# TP_IHM_CONNECTOR.net
KiCad netlist of a schematic drawn in Altium Designer
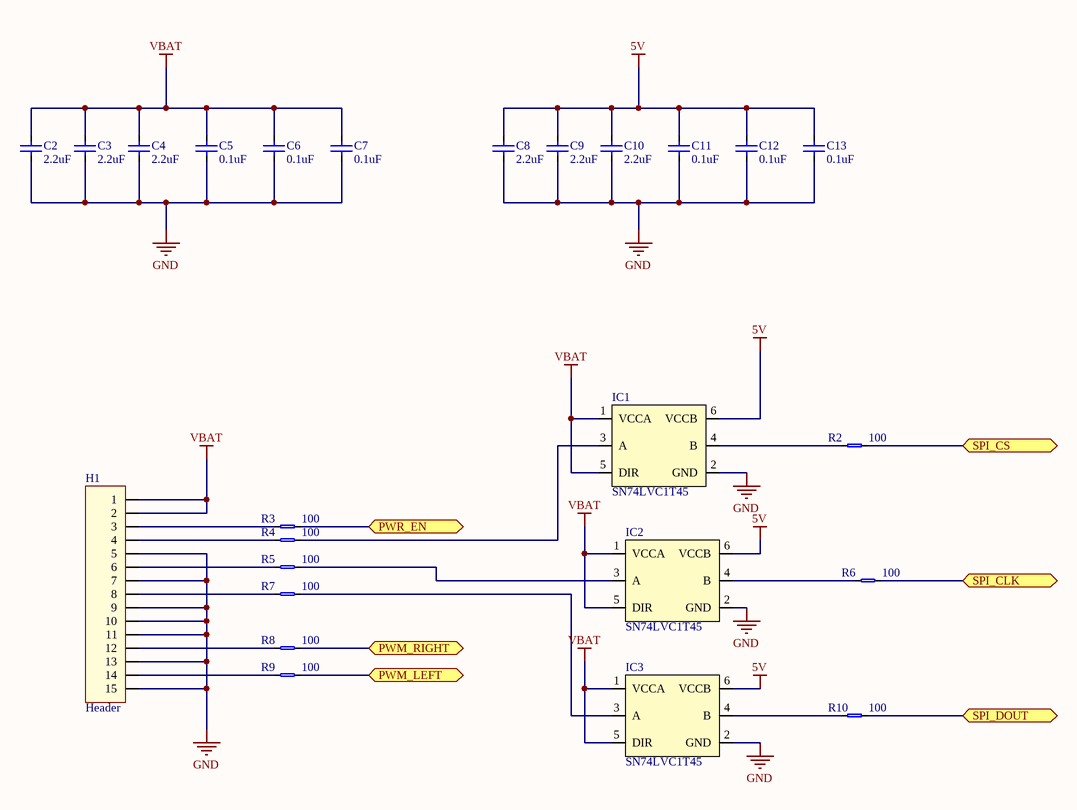
[diagram p0: TP_IHM_CONNECTOR.SchDoc]

(export (version "E")
  (design (tool "Eeschema 10.0.6"))
  (components
    (comp (ref "C2")
      (value "2.2uF")
      (footprint "0402_CAP_LD")
      (description "Ceramic Capacitor")
      (fields (field (name "Comment") "CerCap"))
      (libsource (lib "TpGivenLib") (part "CerCap"))
    )
    (comp (ref "C3")
      (value "2.2uF")
      (footprint "0402_CAP_LD")
      (description "Ceramic Capacitor")
      (fields (field (name "Comment") "CerCap"))
      (libsource (lib "TpGivenLib") (part "CerCap"))
    )
    (comp (ref "C4")
      (value "2.2uF")
      (footprint "0402_CAP_LD")
      (description "Ceramic Capacitor")
      (fields (field (name "Comment") "CerCap"))
      (libsource (lib "TpGivenLib") (part "CerCap"))
    )
    (comp (ref "C5")
      (value "0.1uF")
      (footprint "0402_CAP_LD")
      (description "Ceramic Capacitor")
      (fields (field (name "Comment") "CerCap"))
      (libsource (lib "TpGivenLib") (part "CerCap"))
    )
    (comp (ref "C6")
      (value "0.1uF")
      (footprint "0402_CAP_LD")
      (description "Ceramic Capacitor")
      (fields (field (name "Comment") "CerCap"))
      (libsource (lib "TpGivenLib") (part "CerCap"))
    )
    (comp (ref "C7")
      (value "0.1uF")
      (footprint "0402_CAP_LD")
      (description "Ceramic Capacitor")
      (fields (field (name "Comment") "CerCap"))
      (libsource (lib "TpGivenLib") (part "CerCap"))
    )
    (comp (ref "C8")
      (value "2.2uF")
      (footprint "0402_CAP_LD")
      (description "Ceramic Capacitor")
      (fields (field (name "Comment") "CerCap"))
      (libsource (lib "TpGivenLib") (part "CerCap"))
    )
    (comp (ref "C9")
      (value "2.2uF")
      (footprint "0402_CAP_LD")
      (description "Ceramic Capacitor")
      (fields (field (name "Comment") "CerCap"))
      (libsource (lib "TpGivenLib") (part "CerCap"))
    )
    (comp (ref "C10")
      (value "2.2uF")
      (footprint "0402_CAP_LD")
      (description "Ceramic Capacitor")
      (fields (field (name "Comment") "CerCap"))
      (libsource (lib "TpGivenLib") (part "CerCap"))
    )
    (comp (ref "C11")
      (value "0.1uF")
      (footprint "0402_CAP_LD")
      (description "Ceramic Capacitor")
      (fields (field (name "Comment") "CerCap"))
      (libsource (lib "TpGivenLib") (part "CerCap"))
    )
    (comp (ref "C12")
      (value "0.1uF")
      (footprint "0402_CAP_LD")
      (description "Ceramic Capacitor")
      (fields (field (name "Comment") "CerCap"))
      (libsource (lib "TpGivenLib") (part "CerCap"))
    )
    (comp (ref "C13")
      (value "0.1uF")
      (footprint "0402_CAP_LD")
      (description "Ceramic Capacitor")
      (fields (field (name "Comment") "CerCap"))
      (libsource (lib "TpGivenLib") (part "CerCap"))
    )
    (comp (ref "H1")
      (value "Header")
      (footprint "653115131822")
      (description "Header 15x1")
      (libsource (lib "TpGiven") (part "HEADER_15x1"))
    )
    (comp (ref "IC1")
      (value "SN74LVC1T45")
      (footprint "MO-203AB_LD")
      (description "Single Bit Dual Supply Buffer")
      (libsource (lib "TpGiven") (part "SN74LVC1T45"))
    )
    (comp (ref "IC2")
      (value "SN74LVC1T45")
      (footprint "MO-203AB_LD")
      (description "Single Bit Dual Supply Buffer")
      (libsource (lib "TpGiven") (part "SN74LVC1T45"))
    )
    (comp (ref "IC3")
      (value "SN74LVC1T45")
      (footprint "MO-203AB_LD")
      (description "Single Bit Dual Supply Buffer")
      (libsource (lib "TpGiven") (part "SN74LVC1T45"))
    )
    (comp (ref "R2")
      (value "100")
      (footprint "0603_RES_LD")
      (description "Resistor")
      (libsource (lib "TpGiven") (part "Resistor"))
    )
    (comp (ref "R3")
      (value "100")
      (footprint "0603_RES_LD")
      (description "Resistor")
      (libsource (lib "TpGiven") (part "Resistor"))
    )
    (comp (ref "R4")
      (value "100")
      (footprint "0603_RES_LD")
      (description "Resistor")
      (libsource (lib "TpGiven") (part "Resistor"))
    )
    (comp (ref "R5")
      (value "100")
      (footprint "0603_RES_LD")
      (description "Resistor")
      (libsource (lib "TpGiven") (part "Resistor"))
    )
    (comp (ref "R6")
      (value "100")
      (footprint "0603_RES_LD")
      (description "Resistor")
      (libsource (lib "TpGiven") (part "Resistor"))
    )
    (comp (ref "R7")
      (value "100")
      (footprint "0603_RES_LD")
      (description "Resistor")
      (libsource (lib "TpGiven") (part "Resistor"))
    )
    (comp (ref "R8")
      (value "100")
      (footprint "0603_RES_LD")
      (description "Resistor")
      (libsource (lib "TpGiven") (part "Resistor"))
    )
    (comp (ref "R9")
      (value "100")
      (footprint "0603_RES_LD")
      (description "Resistor")
      (libsource (lib "TpGiven") (part "Resistor"))
    )
    (comp (ref "R10")
      (value "100")
      (footprint "0603_RES_LD")
      (description "Resistor")
      (libsource (lib "TpGiven") (part "Resistor"))
    )
  )
  (nets
    (net (code "1") (name "/PWM_LEFT") (class "Default")
      (node (ref "R9") (pin "2") (pinfunction "2_2") (pintype "passive"))
    )
    (net (code "2") (name "/PWM_RIGHT") (class "Default")
      (node (ref "R8") (pin "2") (pinfunction "2_2") (pintype "passive"))
    )
    (net (code "3") (name "/PWR_EN") (class "Default")
      (node (ref "R3") (pin "2") (pinfunction "2_2") (pintype "passive"))
    )
    (net (code "4") (name "/SPI_CLK") (class "Default")
      (node (ref "R6") (pin "2") (pinfunction "2_2") (pintype "passive"))
    )
    (net (code "5") (name "/SPI_CS") (class "Default")
      (node (ref "R2") (pin "2") (pinfunction "2_2") (pintype "passive"))
    )
    (net (code "6") (name "/SPI_DOUT") (class "Default")
      (node (ref "R10") (pin "2") (pinfunction "2_2") (pintype "passive"))
    )
    (net (code "7") (name "5V") (class "Default")
      (node (ref "C10") (pin "2") (pinfunction "2_2") (pintype "passive"))
      (node (ref "C11") (pin "2") (pinfunction "2_2") (pintype "passive"))
      (node (ref "C12") (pin "2") (pinfunction "2_2") (pintype "passive"))
      (node (ref "C13") (pin "2") (pinfunction "2_2") (pintype "passive"))
      (node (ref "C8") (pin "2") (pinfunction "2_2") (pintype "passive"))
      (node (ref "C9") (pin "2") (pinfunction "2_2") (pintype "passive"))
      (node (ref "IC1") (pin "6") (pinfunction "VCCB_6") (pintype "passive"))
      (node (ref "IC2") (pin "6") (pinfunction "VCCB_6") (pintype "passive"))
      (node (ref "IC3") (pin "6") (pinfunction "VCCB_6") (pintype "passive"))
    )
    (net (code "8") (name "GND") (class "Default")
      (node (ref "C10") (pin "1") (pinfunction "1_1") (pintype "passive"))
      (node (ref "C11") (pin "1") (pinfunction "1_1") (pintype "passive"))
      (node (ref "C12") (pin "1") (pinfunction "1_1") (pintype "passive"))
      (node (ref "C13") (pin "1") (pinfunction "1_1") (pintype "passive"))
      (node (ref "C2") (pin "1") (pinfunction "1_1") (pintype "passive"))
      (node (ref "C3") (pin "1") (pinfunction "1_1") (pintype "passive"))
      (node (ref "C4") (pin "1") (pinfunction "1_1") (pintype "passive"))
      (node (ref "C5") (pin "1") (pinfunction "1_1") (pintype "passive"))
      (node (ref "C6") (pin "1") (pinfunction "1_1") (pintype "passive"))
      (node (ref "C7") (pin "1") (pinfunction "1_1") (pintype "passive"))
      (node (ref "C8") (pin "1") (pinfunction "1_1") (pintype "passive"))
      (node (ref "C9") (pin "1") (pinfunction "1_1") (pintype "passive"))
      (node (ref "H1") (pin "10") (pinfunction "10_10") (pintype "passive"))
      (node (ref "H1") (pin "11") (pinfunction "11_11") (pintype "passive"))
      (node (ref "H1") (pin "13") (pinfunction "13_13") (pintype "passive"))
      (node (ref "H1") (pin "15") (pinfunction "15_15") (pintype "passive"))
      (node (ref "H1") (pin "5") (pinfunction "5_5") (pintype "passive"))
      (node (ref "H1") (pin "7") (pinfunction "7_7") (pintype "passive"))
      (node (ref "H1") (pin "9") (pinfunction "9_9") (pintype "passive"))
      (node (ref "IC1") (pin "2") (pinfunction "GND_2") (pintype "passive"))
      (node (ref "IC2") (pin "2") (pinfunction "GND_2") (pintype "passive"))
      (node (ref "IC3") (pin "2") (pinfunction "GND_2") (pintype "passive"))
    )
    (net (code "9") (name "Net-(H1-Pad3)") (class "Default")
      (node (ref "H1") (pin "3") (pinfunction "3_3") (pintype "passive"))
      (node (ref "R3") (pin "1") (pinfunction "1_1") (pintype "passive"))
    )
    (net (code "10") (name "Net-(H1-Pad4)") (class "Default")
      (node (ref "H1") (pin "4") (pinfunction "4_4") (pintype "passive"))
      (node (ref "R4") (pin "1") (pinfunction "1_1") (pintype "passive"))
    )
    (net (code "11") (name "Net-(H1-Pad6)") (class "Default")
      (node (ref "H1") (pin "6") (pinfunction "6_6") (pintype "passive"))
      (node (ref "R5") (pin "1") (pinfunction "1_1") (pintype "passive"))
    )
    (net (code "12") (name "Net-(H1-Pad8)") (class "Default")
      (node (ref "H1") (pin "8") (pinfunction "8_8") (pintype "passive"))
      (node (ref "R7") (pin "1") (pinfunction "1_1") (pintype "passive"))
    )
    (net (code "13") (name "Net-(H1-Pad12)") (class "Default")
      (node (ref "H1") (pin "12") (pinfunction "12_12") (pintype "passive"))
      (node (ref "R8") (pin "1") (pinfunction "1_1") (pintype "passive"))
    )
    (net (code "14") (name "Net-(H1-Pad14)") (class "Default")
      (node (ref "H1") (pin "14") (pinfunction "14_14") (pintype "passive"))
      (node (ref "R9") (pin "1") (pinfunction "1_1") (pintype "passive"))
    )
    (net (code "15") (name "Net-(IC1-A)") (class "Default")
      (node (ref "IC1") (pin "3") (pinfunction "A_3") (pintype "passive"))
      (node (ref "R4") (pin "2") (pinfunction "2_2") (pintype "passive"))
    )
    (net (code "16") (name "Net-(IC1-B)") (class "Default")
      (node (ref "IC1") (pin "4") (pinfunction "B_4") (pintype "passive"))
      (node (ref "R2") (pin "1") (pinfunction "1_1") (pintype "passive"))
    )
    (net (code "17") (name "Net-(IC2-A)") (class "Default")
      (node (ref "IC2") (pin "3") (pinfunction "A_3") (pintype "passive"))
      (node (ref "R5") (pin "2") (pinfunction "2_2") (pintype "passive"))
    )
    (net (code "18") (name "Net-(IC2-B)") (class "Default")
      (node (ref "IC2") (pin "4") (pinfunction "B_4") (pintype "passive"))
      (node (ref "R6") (pin "1") (pinfunction "1_1") (pintype "passive"))
    )
    (net (code "19") (name "Net-(IC3-A)") (class "Default")
      (node (ref "IC3") (pin "3") (pinfunction "A_3") (pintype "passive"))
      (node (ref "R7") (pin "2") (pinfunction "2_2") (pintype "passive"))
    )
    (net (code "20") (name "Net-(IC3-B)") (class "Default")
      (node (ref "IC3") (pin "4") (pinfunction "B_4") (pintype "passive"))
      (node (ref "R10") (pin "1") (pinfunction "1_1") (pintype "passive"))
    )
    (net (code "21") (name "VBAT") (class "Default")
      (node (ref "C2") (pin "2") (pinfunction "2_2") (pintype "passive"))
      (node (ref "C3") (pin "2") (pinfunction "2_2") (pintype "passive"))
      (node (ref "C4") (pin "2") (pinfunction "2_2") (pintype "passive"))
      (node (ref "C5") (pin "2") (pinfunction "2_2") (pintype "passive"))
      (node (ref "C6") (pin "2") (pinfunction "2_2") (pintype "passive"))
      (node (ref "C7") (pin "2") (pinfunction "2_2") (pintype "passive"))
      (node (ref "H1") (pin "1") (pinfunction "1_1") (pintype "passive"))
      (node (ref "H1") (pin "2") (pinfunction "2_2") (pintype "passive"))
      (node (ref "IC1") (pin "1") (pinfunction "VCCA_1") (pintype "passive"))
      (node (ref "IC1") (pin "5") (pinfunction "DIR_5") (pintype "passive"))
      (node (ref "IC2") (pin "1") (pinfunction "VCCA_1") (pintype "passive"))
      (node (ref "IC2") (pin "5") (pinfunction "DIR_5") (pintype "passive"))
      (node (ref "IC3") (pin "1") (pinfunction "VCCA_1") (pintype "passive"))
      (node (ref "IC3") (pin "5") (pinfunction "DIR_5") (pintype "passive"))
    )
  )
)
